# SparkFun_Qwiic_Thermocouple_Amplifier.net
KiCad netlist of a schematic drawn in EAGLE
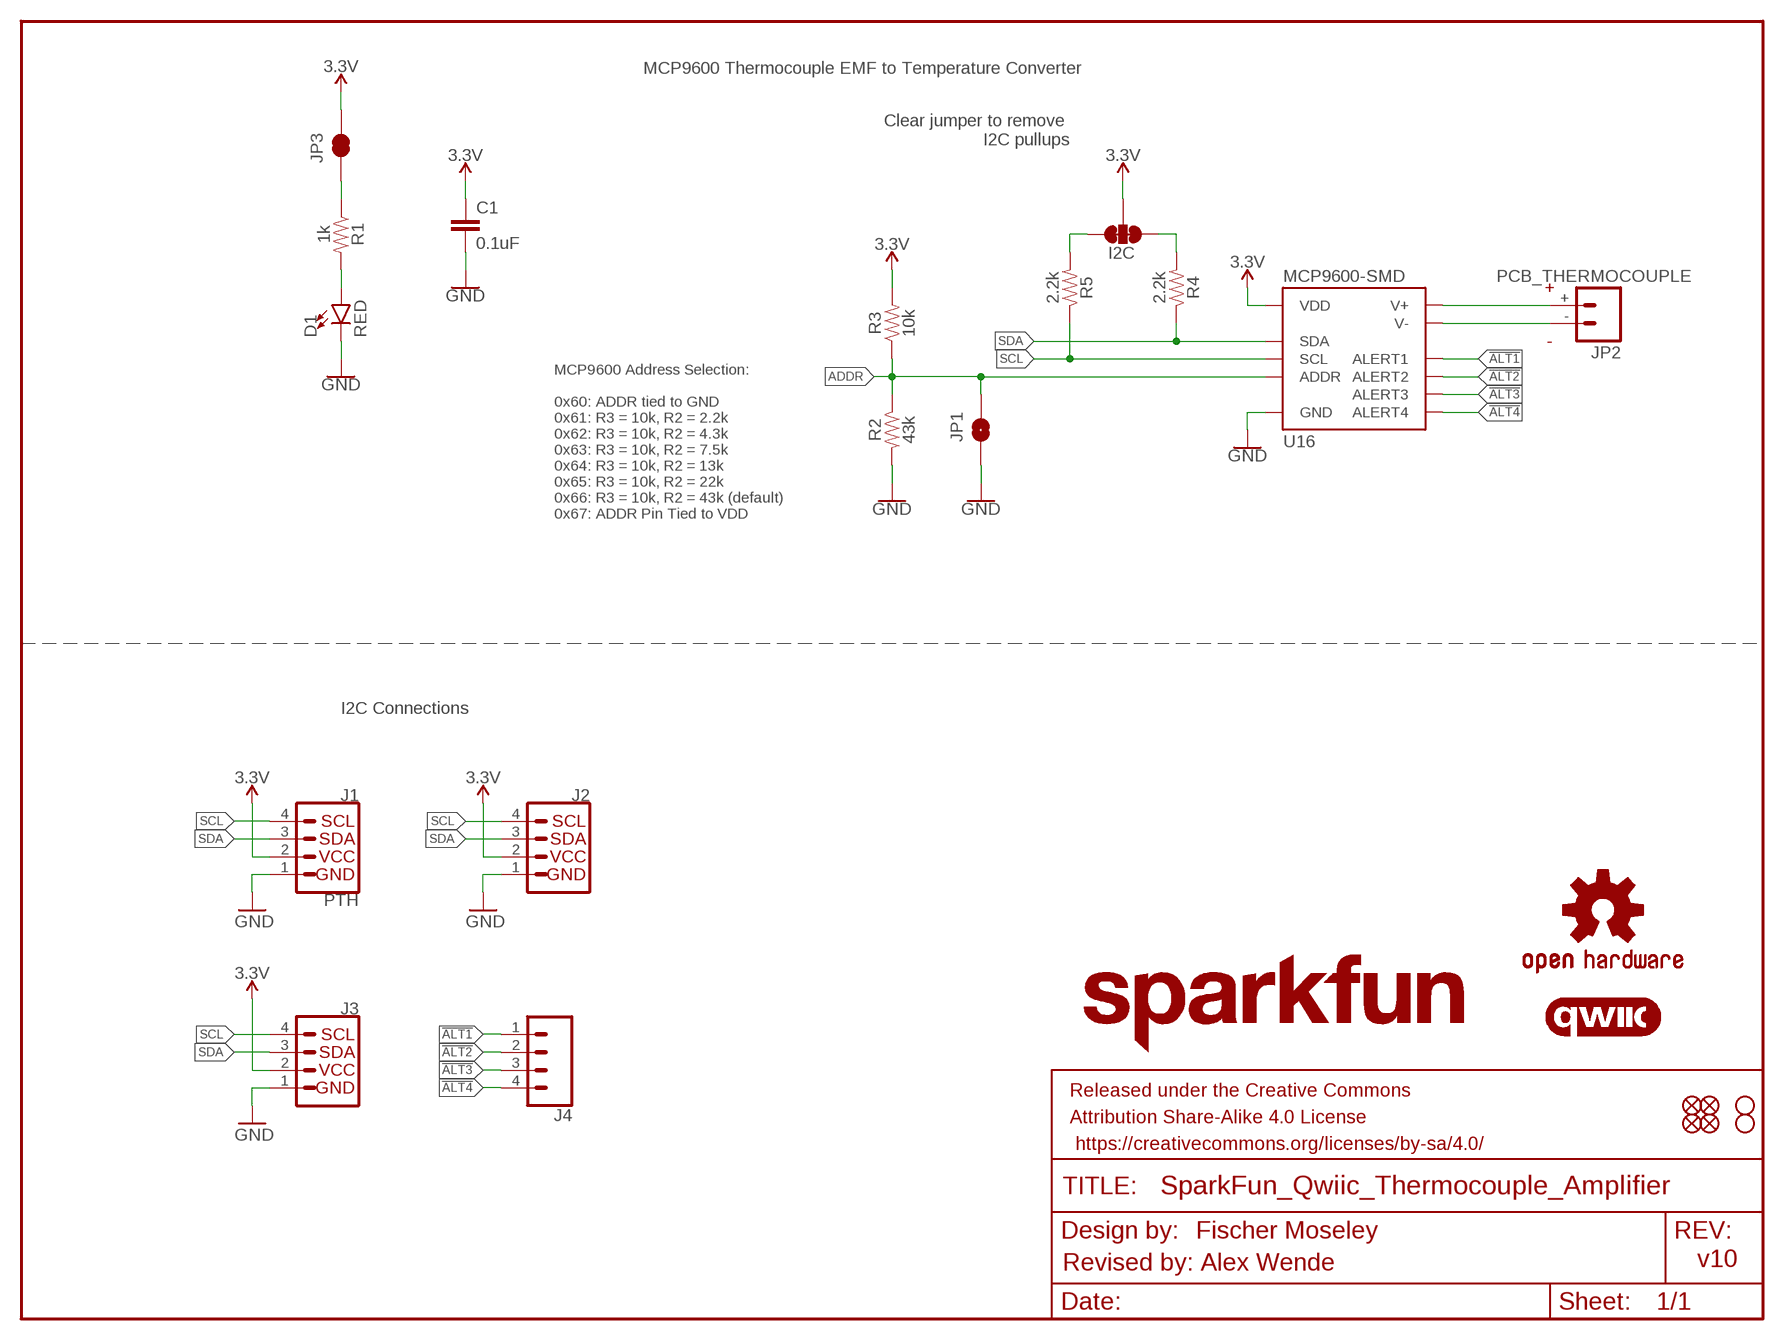
[diagram p0: schematic, sheet 1]

(export (version "E")
  (design (tool "Eeschema 10.0.6"))
  (components
    (comp (ref "C1")
      (value "0.1uF")
      (footprint "eagle-import:0603")
      (libsource (lib "eagle-import") (part "0.1UF-0603-25V-(+80/-20%)"))
    )
    (comp (ref "D1")
      (value "RED")
      (footprint "eagle-import:LED-0603")
      (libsource (lib "eagle-import") (part "LED-RED0603"))
    )
    (comp (ref "FD1")
      (value "FIDUCIAL1X2")
      (footprint "eagle-import:FIDUCIAL-1X2")
      (libsource (lib "eagle-import") (part "FIDUCIAL1X2"))
    )
    (comp (ref "FD2")
      (value "FIDUCIAL1X2")
      (footprint "eagle-import:FIDUCIAL-1X2")
      (libsource (lib "eagle-import") (part "FIDUCIAL1X2"))
    )
    (comp (ref "FD3")
      (value "FIDUCIAL1X2")
      (footprint "eagle-import:FIDUCIAL-1X2")
      (libsource (lib "eagle-import") (part "FIDUCIAL1X2"))
    )
    (comp (ref "FD4")
      (value "FIDUCIAL1X2")
      (footprint "eagle-import:FIDUCIAL-1X2")
      (libsource (lib "eagle-import") (part "FIDUCIAL1X2"))
    )
    (comp (ref "FRAME1")
      (value "FRAME-LETTER")
      (footprint "eagle-import:CREATIVE_COMMONS")
      (libsource (lib "eagle-import") (part "FRAME-LETTER"))
    )
    (comp (ref "I2C")
      (value "JUMPER-SMT_3_2-NC_TRACE_SILK")
      (footprint "eagle-import:SMT-JUMPER_3_2-NC_TRACE_SILK")
      (libsource (lib "eagle-import") (part "JUMPER-SMT_3_2-NC_TRACE_SILK"))
    )
    (comp (ref "J1")
      (value "PTH")
      (footprint "eagle-import:1X04_NO_SILK")
      (libsource (lib "eagle-import") (part "I2C_STANDARD_NO_SILK"))
    )
    (comp (ref "J2")
      (value "QWIIC_CONNECTORJS-1MM")
      (footprint "eagle-import:JST04_1MM_RA")
      (libsource (lib "eagle-import") (part "QWIIC_CONNECTORJS-1MM"))
    )
    (comp (ref "J3")
      (value "QWIIC_CONNECTORJS-1MM")
      (footprint "eagle-import:JST04_1MM_RA")
      (libsource (lib "eagle-import") (part "QWIIC_CONNECTORJS-1MM"))
    )
    (comp (ref "J4")
      (value "CONN_041X04_NO_SILK")
      (footprint "eagle-import:1X04_NO_SILK")
      (libsource (lib "eagle-import") (part "CONN_041X04_NO_SILK"))
    )
    (comp (ref "JP1")
      (value "JUMPER-SMT_2_NO_SILK")
      (footprint "eagle-import:SMT-JUMPER_2_NO_SILK")
      (libsource (lib "eagle-import") (part "JUMPER-SMT_2_NO_SILK"))
    )
    (comp (ref "JP2")
      (value "PCB_THERMOCOUPLE")
      (footprint "eagle-import:PCC-SMP")
      (libsource (lib "eagle-import") (part "PCB_THERMOCOUPLE"))
    )
    (comp (ref "JP3")
      (value "JUMPER-SMT_2_NC_TRACE_SILK")
      (footprint "eagle-import:SMT-JUMPER_2_NC_TRACE_SILK")
      (libsource (lib "eagle-import") (part "JUMPER-SMT_2_NC_TRACE_SILK"))
    )
    (comp (ref "JP8")
      (value "STAND-OFF")
      (footprint "eagle-import:STAND-OFF")
      (libsource (lib "eagle-import") (part "STAND-OFF"))
    )
    (comp (ref "JP9")
      (value "STAND-OFF")
      (footprint "eagle-import:STAND-OFF")
      (libsource (lib "eagle-import") (part "STAND-OFF"))
    )
    (comp (ref "LOGO1")
      (value "OSHW-LOGOMINI")
      (footprint "eagle-import:OSHW-LOGO-MINI")
      (libsource (lib "eagle-import") (part "OSHW-LOGOMINI"))
    )
    (comp (ref "LOGO2")
      (value "SFE_LOGO_NAME.1_INCH")
      (footprint "eagle-import:SFE_LOGO_NAME_.1")
      (libsource (lib "eagle-import") (part "SFE_LOGO_NAME.1_INCH"))
    )
    (comp (ref "LOGO3")
      (value "QWIIC_LOGO_5MM")
      (footprint "eagle-import:QWIIC_5MM")
      (libsource (lib "eagle-import") (part "QWIIC_LOGO_5MM"))
    )
    (comp (ref "R1")
      (value "1k")
      (footprint "eagle-import:0603")
      (libsource (lib "eagle-import") (part "1KOHM-0603-1/10W-1%"))
    )
    (comp (ref "R2")
      (value "43k")
      (footprint "eagle-import:0603")
      (libsource (lib "eagle-import") (part "43KOHM-0603-1/10W-1%"))
    )
    (comp (ref "R3")
      (value "10k")
      (footprint "eagle-import:0603")
      (libsource (lib "eagle-import") (part "10KOHM-0603-1/10W-1%"))
    )
    (comp (ref "R4")
      (value "2.2k")
      (footprint "eagle-import:0603")
      (libsource (lib "eagle-import") (part "2.2KOHM-0603-1/10W-1%"))
    )
    (comp (ref "R5")
      (value "2.2k")
      (footprint "eagle-import:0603")
      (libsource (lib "eagle-import") (part "2.2KOHM-0603-1/10W-1%"))
    )
    (comp (ref "U16")
      (value "MCP9600-SMD")
      (footprint "eagle-import:MQFN-20")
      (libsource (lib "eagle-import") (part "MCP9600-SMD"))
    )
  )
  (nets
    (net (code "1") (name "/~{ALT1}") (class "Default")
      (node (ref "J4") (pin "1") (pinfunction "1_1") (pintype "passive"))
      (node (ref "U16") (pin "11") (pinfunction "ALERT1_11") (pintype "bidirectional"))
    )
    (net (code "2") (name "/~{ALT2}") (class "Default")
      (node (ref "J4") (pin "2") (pinfunction "2_2") (pintype "passive"))
      (node (ref "U16") (pin "12") (pinfunction "ALERT2_12") (pintype "bidirectional"))
    )
    (net (code "3") (name "/~{ALT3}") (class "Default")
      (node (ref "J4") (pin "3") (pinfunction "3_3") (pintype "passive"))
      (node (ref "U16") (pin "14") (pinfunction "ALERT3_14") (pintype "bidirectional"))
    )
    (net (code "4") (name "/~{ALT4}") (class "Default")
      (node (ref "J4") (pin "4") (pinfunction "4_4") (pintype "passive"))
      (node (ref "U16") (pin "15") (pinfunction "ALERT4_15") (pintype "bidirectional"))
    )
    (net (code "5") (name "3.3V") (class "Default")
      (node (ref "C1") (pin "1") (pinfunction "1_1") (pintype "passive"))
      (node (ref "I2C") (pin "2") (pinfunction "2_2") (pintype "passive"))
      (node (ref "J1") (pin "2") (pinfunction "VCC_2") (pintype "power_in"))
      (node (ref "J2") (pin "2") (pinfunction "2_2") (pintype "power_in"))
      (node (ref "J3") (pin "2") (pinfunction "2_2") (pintype "power_in"))
      (node (ref "JP3") (pin "2") (pinfunction "2_2") (pintype "passive"))
      (node (ref "R3") (pin "2") (pinfunction "2_2") (pintype "passive"))
      (node (ref "U16") (pin "8") (pinfunction "VDD_8") (pintype "bidirectional"))
    )
    (net (code "6") (name "ADDR") (class "Default")
      (node (ref "JP1") (pin "1") (pinfunction "1_1") (pintype "passive"))
      (node (ref "R2") (pin "1") (pinfunction "1_1") (pintype "passive"))
      (node (ref "R3") (pin "1") (pinfunction "1_1") (pintype "passive"))
      (node (ref "U16") (pin "16") (pinfunction "ADDR_16") (pintype "bidirectional"))
    )
    (net (code "7") (name "GND") (class "Default")
      (node (ref "C1") (pin "2") (pinfunction "2_2") (pintype "passive"))
      (node (ref "D1") (pin "C") (pinfunction "C_C") (pintype "passive"))
      (node (ref "J1") (pin "1") (pinfunction "GND_1") (pintype "power_in"))
      (node (ref "J2") (pin "1") (pinfunction "1_1") (pintype "power_in"))
      (node (ref "J3") (pin "1") (pinfunction "1_1") (pintype "power_in"))
      (node (ref "JP1") (pin "2") (pinfunction "2_2") (pintype "passive"))
      (node (ref "R2") (pin "2") (pinfunction "2_2") (pintype "passive"))
      (node (ref "U16") (pin "1") (pinfunction "GND_1") (pintype "bidirectional"))
      (node (ref "U16") (pin "10") (pinfunction "GND_10") (pintype "bidirectional"))
      (node (ref "U16") (pin "13") (pinfunction "GND_13") (pintype "bidirectional"))
      (node (ref "U16") (pin "17") (pinfunction "GND_17") (pintype "bidirectional"))
      (node (ref "U16") (pin "18") (pinfunction "GND_18") (pintype "bidirectional"))
      (node (ref "U16") (pin "21") (pinfunction "GND_21") (pintype "bidirectional"))
      (node (ref "U16") (pin "3") (pinfunction "GND_3") (pintype "bidirectional"))
      (node (ref "U16") (pin "5") (pinfunction "GND_5") (pintype "bidirectional"))
      (node (ref "U16") (pin "6") (pinfunction "GND_6") (pintype "bidirectional"))
      (node (ref "U16") (pin "7") (pinfunction "GND_7") (pintype "bidirectional"))
      (node (ref "U16") (pin "9") (pinfunction "GND_9") (pintype "bidirectional"))
    )
    (net (code "8") (name "Net-(D1-PadA)") (class "Default")
      (node (ref "D1") (pin "A") (pinfunction "A_A") (pintype "passive"))
      (node (ref "R1") (pin "2") (pinfunction "2_2") (pintype "passive"))
    )
    (net (code "9") (name "Net-(I2C-Pad1)") (class "Default")
      (node (ref "I2C") (pin "1") (pinfunction "1_1") (pintype "passive"))
      (node (ref "R5") (pin "2") (pinfunction "2_2") (pintype "passive"))
    )
    (net (code "10") (name "Net-(I2C-Pad3)") (class "Default")
      (node (ref "I2C") (pin "3") (pinfunction "3_3") (pintype "passive"))
      (node (ref "R4") (pin "2") (pinfunction "2_2") (pintype "passive"))
    )
    (net (code "11") (name "Net-(JP3-Pad1)") (class "Default")
      (node (ref "JP3") (pin "1") (pinfunction "1_1") (pintype "passive"))
      (node (ref "R1") (pin "1") (pinfunction "1_1") (pintype "passive"))
    )
    (net (code "12") (name "Net-(U16-V+)") (class "Default")
      (node (ref "JP2") (pin "+") (pinfunction "+_+") (pintype "passive"))
      (node (ref "U16") (pin "2") (pinfunction "V+_2") (pintype "bidirectional"))
    )
    (net (code "13") (name "Net-(U16-V-)") (class "Default")
      (node (ref "JP2") (pin "-") (pinfunction "-_-") (pintype "passive"))
      (node (ref "U16") (pin "4") (pinfunction "V-_4") (pintype "bidirectional"))
    )
    (net (code "14") (name "SCL") (class "Default")
      (node (ref "J1") (pin "4") (pinfunction "SCL_4") (pintype "passive"))
      (node (ref "J2") (pin "4") (pinfunction "4_4") (pintype "passive"))
      (node (ref "J3") (pin "4") (pinfunction "4_4") (pintype "passive"))
      (node (ref "R5") (pin "1") (pinfunction "1_1") (pintype "passive"))
      (node (ref "U16") (pin "19") (pinfunction "SCL_19") (pintype "bidirectional"))
    )
    (net (code "15") (name "SDA") (class "Default")
      (node (ref "J1") (pin "3") (pinfunction "SDA_3") (pintype "passive"))
      (node (ref "J2") (pin "3") (pinfunction "3_3") (pintype "passive"))
      (node (ref "J3") (pin "3") (pinfunction "3_3") (pintype "passive"))
      (node (ref "R4") (pin "1") (pinfunction "1_1") (pintype "passive"))
      (node (ref "U16") (pin "20") (pinfunction "SDA_20") (pintype "bidirectional"))
    )
  )
)
